# Sheet1.net
KiCad netlist of a schematic drawn in Altium Designer
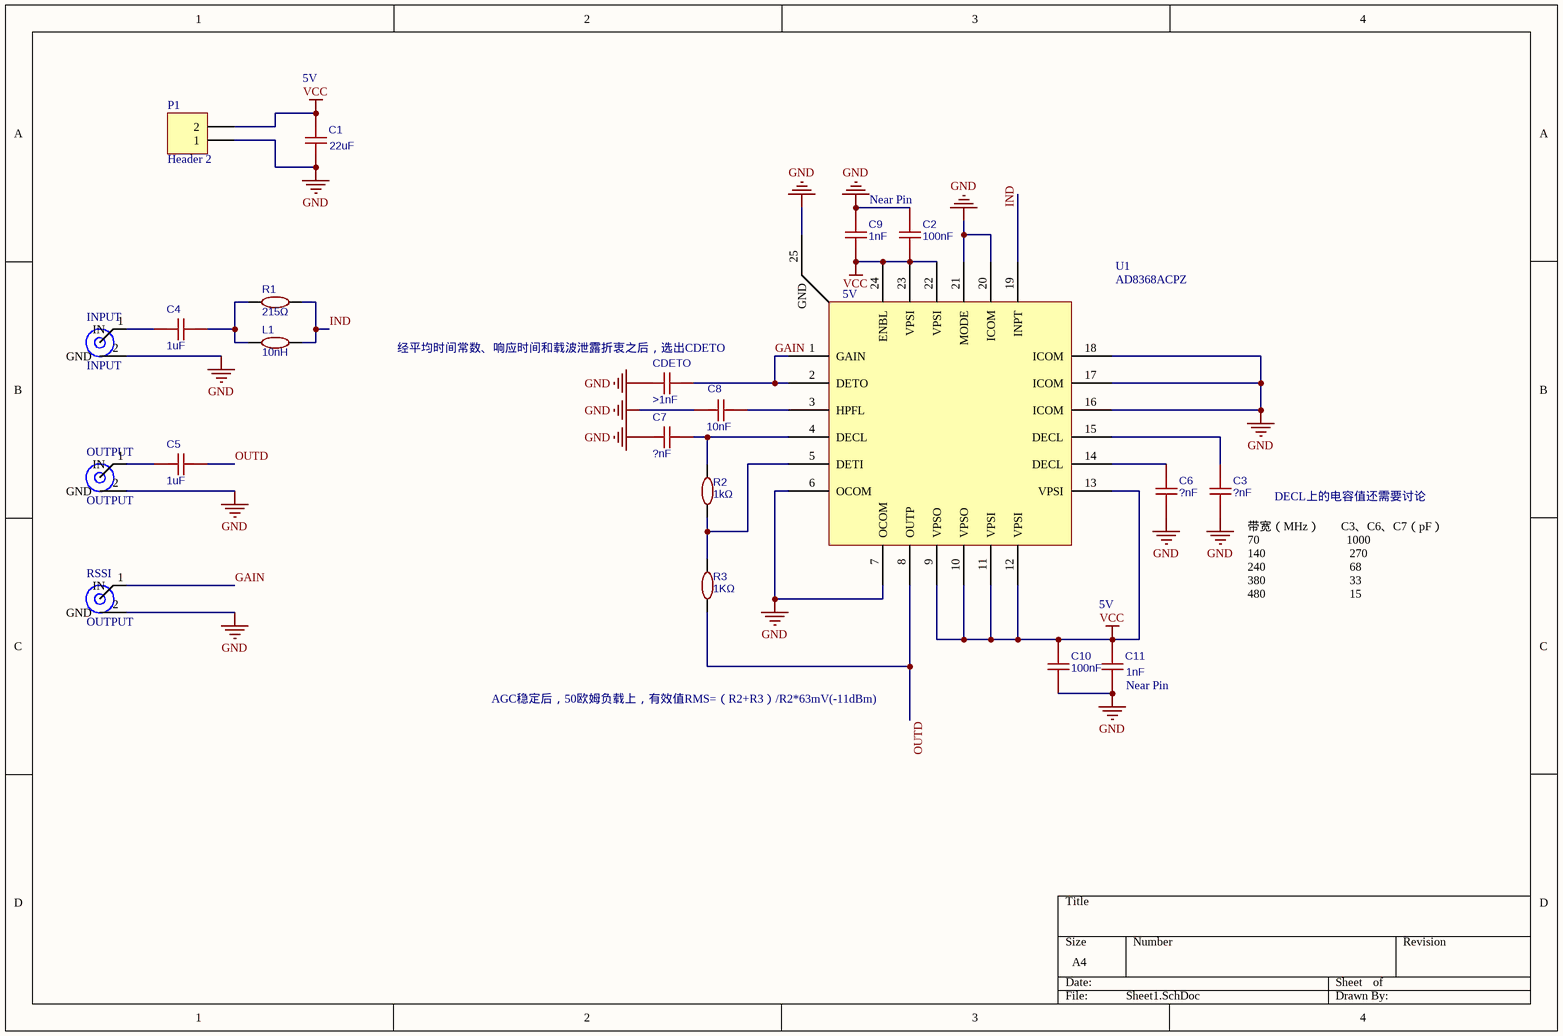
[diagram p0: Sheet1.SchDoc]

(export (version "E")
  (design (tool "Eeschema 10.0.6"))
  (components
    (comp (ref "C1")
      (value "22uF")
      (footprint "0603")
      (fields
        (field (name "BOM_SUPPLIER PART") "C108079")
        (field (name "BOM_MANUFACTURER PART") "CC0603KRX7R7BB104")
        (field (name "CONTRIBUTOR") "LCSC")
      )
      (libsource (lib "AGC") (part "C"))
    )
    (comp (ref "C2")
      (value "100nF")
      (footprint "0603")
      (fields
        (field (name "BOM_SUPPLIER PART") "C108079")
        (field (name "BOM_MANUFACTURER PART") "CC0603KRX7R7BB104")
        (field (name "CONTRIBUTOR") "LCSC")
      )
      (libsource (lib "AGC") (part "C"))
    )
    (comp (ref "C3")
      (value "?nF")
      (footprint "0603")
      (fields
        (field (name "BOM_SUPPLIER PART") "C108079")
        (field (name "BOM_MANUFACTURER PART") "CC0603KRX7R7BB104")
        (field (name "CONTRIBUTOR") "LCSC")
      )
      (libsource (lib "AGC") (part "C"))
    )
    (comp (ref "C4")
      (value "1uF")
      (footprint "0603")
      (fields
        (field (name "BOM_SUPPLIER PART") "C108079")
        (field (name "BOM_MANUFACTURER PART") "CC0603KRX7R7BB104")
        (field (name "CONTRIBUTOR") "LCSC")
      )
      (libsource (lib "AGC") (part "C"))
    )
    (comp (ref "C5")
      (value "1uF")
      (footprint "0603")
      (fields
        (field (name "BOM_SUPPLIER PART") "C108079")
        (field (name "BOM_MANUFACTURER PART") "CC0603KRX7R7BB104")
        (field (name "CONTRIBUTOR") "LCSC")
      )
      (libsource (lib "AGC") (part "C"))
    )
    (comp (ref "C6")
      (value "?nF")
      (footprint "0603")
      (fields
        (field (name "BOM_SUPPLIER PART") "C108079")
        (field (name "BOM_MANUFACTURER PART") "CC0603KRX7R7BB104")
        (field (name "CONTRIBUTOR") "LCSC")
      )
      (libsource (lib "AGC") (part "C"))
    )
    (comp (ref "C7")
      (value "?nF")
      (footprint "0603")
      (fields
        (field (name "BOM_SUPPLIER PART") "C108079")
        (field (name "BOM_MANUFACTURER PART") "CC0603KRX7R7BB104")
        (field (name "CONTRIBUTOR") "LCSC")
      )
      (libsource (lib "AGC") (part "C"))
    )
    (comp (ref "C8")
      (value "10nF")
      (footprint "0603")
      (fields
        (field (name "BOM_SUPPLIER PART") "C108079")
        (field (name "BOM_MANUFACTURER PART") "CC0603KRX7R7BB104")
        (field (name "CONTRIBUTOR") "LCSC")
      )
      (libsource (lib "AGC") (part "C"))
    )
    (comp (ref "C9")
      (value "1nF")
      (footprint "0603")
      (fields
        (field (name "BOM_SUPPLIER PART") "C108079")
        (field (name "BOM_MANUFACTURER PART") "CC0603KRX7R7BB104")
        (field (name "CONTRIBUTOR") "LCSC")
      )
      (libsource (lib "AGC") (part "C"))
    )
    (comp (ref "C10")
      (value "100nF")
      (footprint "0603")
      (fields
        (field (name "BOM_SUPPLIER PART") "C108079")
        (field (name "BOM_MANUFACTURER PART") "CC0603KRX7R7BB104")
        (field (name "CONTRIBUTOR") "LCSC")
      )
      (libsource (lib "AGC") (part "C"))
    )
    (comp (ref "C11")
      (value "1nF")
      (footprint "0603")
      (fields
        (field (name "BOM_SUPPLIER PART") "C108079")
        (field (name "BOM_MANUFACTURER PART") "CC0603KRX7R7BB104")
        (field (name "CONTRIBUTOR") "LCSC")
      )
      (libsource (lib "AGC") (part "C"))
    )
    (comp (ref "CDETO")
      (value ">1nF")
      (footprint "0603")
      (fields
        (field (name "BOM_SUPPLIER PART") "C108079")
        (field (name "BOM_MANUFACTURER PART") "CC0603KRX7R7BB104")
        (field (name "CONTRIBUTOR") "LCSC")
      )
      (libsource (lib "AGC") (part "C"))
    )
    (comp (ref "INPUT") (value "INPUT") (footprint "SMA-2") (libsource (lib "AGC") (part "SMA")))
    (comp (ref "L1")
      (value "10nH")
      (footprint "0603")
      (fields
        (field (name "BOM_MANUFACTURER PART") "TC0350D1002T5E")
        (field (name "BOM_SUPPLIER PART") "C64266")
      )
      (libsource (lib "AGC") (part "R"))
    )
    (comp (ref "OUTPUT") (value "OUTPUT") (footprint "SMA-2") (libsource (lib "AGC") (part "SMA")))
    (comp (ref "P1")
      (value "Header 2")
      (footprint "HDR1X2")
      (description "Header, 2-Pin")
      (fields (field (name "PUBLISHER") "Altium Limited"))
      (libsource (lib "Miscellaneous Connectors") (part "Header 2"))
    )
    (comp (ref "R1")
      (value "215Ω")
      (footprint "0603")
      (fields
        (field (name "BOM_MANUFACTURER PART") "TC0350D1002T5E")
        (field (name "BOM_SUPPLIER PART") "C64266")
      )
      (libsource (lib "AGC") (part "R"))
    )
    (comp (ref "R2")
      (value "1kΩ")
      (footprint "0603")
      (fields
        (field (name "BOM_MANUFACTURER PART") "TC0350D1002T5E")
        (field (name "BOM_SUPPLIER PART") "C64266")
      )
      (libsource (lib "AGC") (part "R"))
    )
    (comp (ref "R3")
      (value "1KΩ")
      (footprint "0603")
      (fields
        (field (name "BOM_MANUFACTURER PART") "TC0350D1002T5E")
        (field (name "BOM_SUPPLIER PART") "C64266")
      )
      (libsource (lib "AGC") (part "R"))
    )
    (comp (ref "RSSI") (value "OUTPUT") (footprint "SMA-2") (libsource (lib "AGC") (part "SMA")))
    (comp (ref "U1")
      (value "AD8368ACPZ")
      (footprint "LFCSP-24_4X4X05P")
      (libsource (lib "AGC") (part "AD8368"))
    )
  )
  (nets
    (net (code "1") (name "/GAIN") (class "Default")
      (node (ref "CDETO") (pin "1") (pinfunction "1_1") (pintype "passive"))
      (node (ref "RSSI") (pin "1") (pinfunction "IN_1") (pintype "passive"))
      (node (ref "U1") (pin "1") (pinfunction "GAIN_1") (pintype "passive"))
      (node (ref "U1") (pin "2") (pinfunction "DETO_2") (pintype "passive"))
    )
    (net (code "2") (name "/IND") (class "Default")
      (node (ref "L1") (pin "2") (pinfunction "2_2") (pintype "passive"))
      (node (ref "R1") (pin "2") (pinfunction "2_2") (pintype "passive"))
      (node (ref "U1") (pin "19") (pinfunction "INPT_19") (pintype "passive"))
    )
    (net (code "3") (name "/OUTD") (class "Default")
      (node (ref "C5") (pin "1") (pinfunction "1_1") (pintype "passive"))
      (node (ref "R3") (pin "1") (pinfunction "1_1") (pintype "passive"))
      (node (ref "U1") (pin "8") (pinfunction "OUTP_8") (pintype "passive"))
    )
    (net (code "4") (name "GND") (class "Default")
      (node (ref "C1") (pin "1") (pinfunction "1_1") (pintype "passive"))
      (node (ref "C10") (pin "1") (pinfunction "1_1") (pintype "passive"))
      (node (ref "C11") (pin "1") (pinfunction "1_1") (pintype "passive"))
      (node (ref "C2") (pin "1") (pinfunction "1_1") (pintype "passive"))
      (node (ref "C3") (pin "1") (pinfunction "1_1") (pintype "passive"))
      (node (ref "C6") (pin "1") (pinfunction "1_1") (pintype "passive"))
      (node (ref "C7") (pin "2") (pinfunction "2_2") (pintype "passive"))
      (node (ref "C8") (pin "2") (pinfunction "2_2") (pintype "passive"))
      (node (ref "C9") (pin "1") (pinfunction "1_1") (pintype "passive"))
      (node (ref "CDETO") (pin "2") (pinfunction "2_2") (pintype "passive"))
      (node (ref "INPUT") (pin "2") (pinfunction "GND_2") (pintype "passive"))
      (node (ref "OUTPUT") (pin "2") (pinfunction "GND_2") (pintype "passive"))
      (node (ref "P1") (pin "1") (pinfunction "1_1") (pintype "passive"))
      (node (ref "RSSI") (pin "2") (pinfunction "GND_2") (pintype "passive"))
      (node (ref "U1") (pin "16") (pinfunction "ICOM_16") (pintype "passive"))
      (node (ref "U1") (pin "17") (pinfunction "ICOM_17") (pintype "passive"))
      (node (ref "U1") (pin "18") (pinfunction "ICOM_18") (pintype "passive"))
      (node (ref "U1") (pin "20") (pinfunction "ICOM_20") (pintype "passive"))
      (node (ref "U1") (pin "21") (pinfunction "MODE_21") (pintype "passive"))
      (node (ref "U1") (pin "25") (pinfunction "GND_25") (pintype "passive"))
      (node (ref "U1") (pin "6") (pinfunction "OCOM_6") (pintype "passive"))
      (node (ref "U1") (pin "7") (pinfunction "OCOM_7") (pintype "passive"))
    )
    (net (code "5") (name "Net-(C3-Pad2)") (class "Default")
      (node (ref "C3") (pin "2") (pinfunction "2_2") (pintype "passive"))
      (node (ref "U1") (pin "15") (pinfunction "DECL_15") (pintype "passive"))
    )
    (net (code "6") (name "Net-(C4-Pad1)") (class "Default")
      (node (ref "C4") (pin "1") (pinfunction "1_1") (pintype "passive"))
      (node (ref "L1") (pin "1") (pinfunction "1_1") (pintype "passive"))
      (node (ref "R1") (pin "1") (pinfunction "1_1") (pintype "passive"))
    )
    (net (code "7") (name "Net-(C6-Pad2)") (class "Default")
      (node (ref "C6") (pin "2") (pinfunction "2_2") (pintype "passive"))
      (node (ref "U1") (pin "14") (pinfunction "DECL_14") (pintype "passive"))
    )
    (net (code "8") (name "Net-(C7-Pad1)") (class "Default")
      (node (ref "C7") (pin "1") (pinfunction "1_1") (pintype "passive"))
      (node (ref "R2") (pin "2") (pinfunction "2_2") (pintype "passive"))
      (node (ref "U1") (pin "4") (pinfunction "DECL_4") (pintype "passive"))
    )
    (net (code "9") (name "Net-(INPUT-IN)") (class "Default")
      (node (ref "C4") (pin "2") (pinfunction "2_2") (pintype "passive"))
      (node (ref "INPUT") (pin "1") (pinfunction "IN_1") (pintype "passive"))
    )
    (net (code "10") (name "Net-(OUTPUT-IN)") (class "Default")
      (node (ref "C5") (pin "2") (pinfunction "2_2") (pintype "passive"))
      (node (ref "OUTPUT") (pin "1") (pinfunction "IN_1") (pintype "passive"))
    )
    (net (code "11") (name "Net-(U1-DETI)") (class "Default")
      (node (ref "R2") (pin "1") (pinfunction "1_1") (pintype "passive"))
      (node (ref "R3") (pin "2") (pinfunction "2_2") (pintype "passive"))
      (node (ref "U1") (pin "5") (pinfunction "DETI_5") (pintype "passive"))
    )
    (net (code "12") (name "Net-(U1-HPFL)") (class "Default")
      (node (ref "C8") (pin "1") (pinfunction "1_1") (pintype "passive"))
      (node (ref "U1") (pin "3") (pinfunction "HPFL_3") (pintype "passive"))
    )
    (net (code "13") (name "VCC") (class "Default")
      (node (ref "C1") (pin "2") (pinfunction "2_2") (pintype "passive"))
      (node (ref "C10") (pin "2") (pinfunction "2_2") (pintype "passive"))
      (node (ref "C11") (pin "2") (pinfunction "2_2") (pintype "passive"))
      (node (ref "C2") (pin "2") (pinfunction "2_2") (pintype "passive"))
      (node (ref "C9") (pin "2") (pinfunction "2_2") (pintype "passive"))
      (node (ref "P1") (pin "2") (pinfunction "2_2") (pintype "passive"))
      (node (ref "U1") (pin "10") (pinfunction "VPSO_10") (pintype "passive"))
      (node (ref "U1") (pin "11") (pinfunction "VPSI_11") (pintype "passive"))
      (node (ref "U1") (pin "12") (pinfunction "VPSI_12") (pintype "passive"))
      (node (ref "U1") (pin "13") (pinfunction "VPSI_13") (pintype "passive"))
      (node (ref "U1") (pin "22") (pinfunction "VPSI_22") (pintype "passive"))
      (node (ref "U1") (pin "23") (pinfunction "VPSI_23") (pintype "passive"))
      (node (ref "U1") (pin "24") (pinfunction "ENBL_24") (pintype "passive"))
      (node (ref "U1") (pin "9") (pinfunction "VPSO_9") (pintype "passive"))
    )
  )
)
